# schematic.net
KiCad netlist of a schematic drawn in Altium Designer
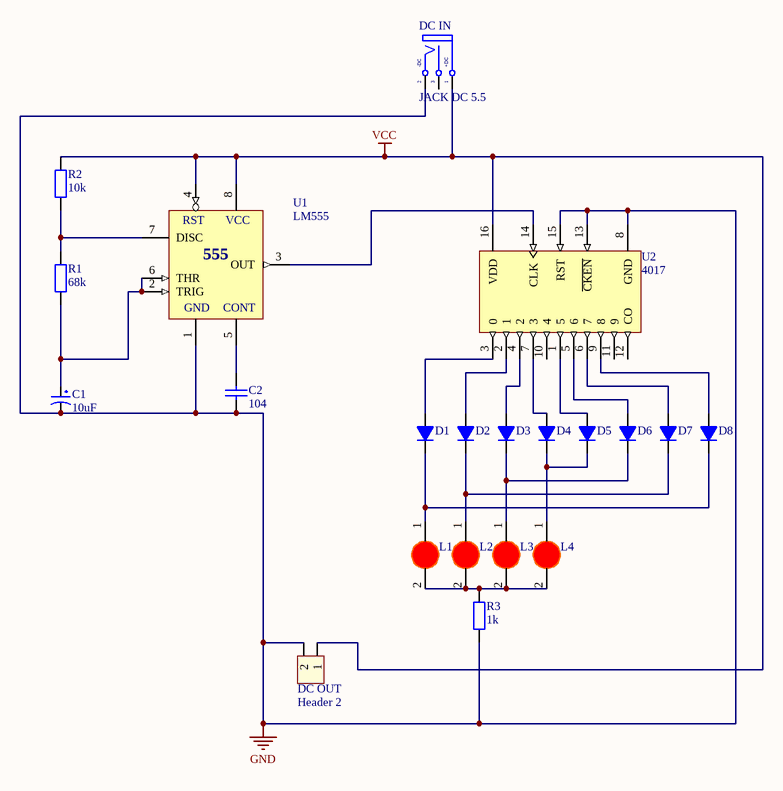
[diagram p0: schematic.SchDoc]

(export (version "E")
  (design (tool "Eeschema 10.0.6"))
  (components
    (comp (ref "C1")
      (value "10uF")
      (footprint "tu hoa 4mm")
      (description "Cắm")
      (libsource (lib "Capacitor") (part "Tu Hoa 10uF 16V 4x7"))
    )
    (comp (ref "C2")
      (value "104")
      (footprint "tu gom")
      (description "Cắm")
      (libsource (lib "Capacitor") (part "Tu gom 104 50V"))
    )
    (comp (ref "D1")
      (value "~")
      (footprint "DIODE 1A")
      (description "Cắm")
      (libsource (lib "Diode") (part "Diode 1N4007"))
    )
    (comp (ref "D2")
      (value "~")
      (footprint "DIODE 1A")
      (description "Cắm")
      (libsource (lib "Diode") (part "Diode 1N4007"))
    )
    (comp (ref "D3")
      (value "~")
      (footprint "DIODE 1A")
      (description "Cắm")
      (libsource (lib "Diode") (part "Diode 1N4007"))
    )
    (comp (ref "D4")
      (value "~")
      (footprint "DIODE 1A")
      (description "Cắm")
      (libsource (lib "Diode") (part "Diode 1N4007"))
    )
    (comp (ref "D5")
      (value "~")
      (footprint "DIODE 1A")
      (description "Cắm")
      (libsource (lib "Diode") (part "Diode 1N4007"))
    )
    (comp (ref "D6")
      (value "~")
      (footprint "DIODE 1A")
      (description "Cắm")
      (libsource (lib "Diode") (part "Diode 1N4007"))
    )
    (comp (ref "D7")
      (value "~")
      (footprint "DIODE 1A")
      (description "Cắm")
      (libsource (lib "Diode") (part "Diode 1N4007"))
    )
    (comp (ref "D8")
      (value "~")
      (footprint "DIODE 1A")
      (description "Cắm")
      (libsource (lib "Diode") (part "Diode 1N4007"))
    )
    (comp (ref "DC IN")
      (value "JACK DC 5.5")
      (footprint "JACK DC 5.5")
      (libsource (lib "Component") (part "JACK DC 5.5"))
    )
    (comp (ref "DC OUT")
      (value "Header 2")
      (footprint "HED2")
      (description "Header 2 (Green)")
      (libsource (lib "My Library") (part "Hed2"))
    )
    (comp (ref "L1")
      (value "~")
      (footprint "LED-3MM-RED")
      (description "Cắm")
      (libsource (lib "Led") (part "LED 3mm Do"))
    )
    (comp (ref "L2")
      (value "~")
      (footprint "LED-3MM-RED")
      (description "Cắm")
      (libsource (lib "Led") (part "LED 3mm Do"))
    )
    (comp (ref "L3")
      (value "~")
      (footprint "LED-3MM-RED")
      (description "Cắm")
      (libsource (lib "Led") (part "LED 3mm Do"))
    )
    (comp (ref "L4")
      (value "~")
      (footprint "LED-3MM-RED")
      (description "Cắm")
      (libsource (lib "Led") (part "LED 3mm Do"))
    )
    (comp (ref "R1")
      (value "68k")
      (footprint "tro vach 1/4w")
      (description "Cắm")
      (libsource (lib "Resistor") (part "Tro Vach 1/4W 5% 68k"))
    )
    (comp (ref "R2")
      (value "10k")
      (footprint "tro vach 1w")
      (description "Cắm")
      (libsource (lib "Resistor") (part "Tro Vach 1W 5% 10k"))
    )
    (comp (ref "R3")
      (value "1k")
      (footprint "tro vach 1w")
      (description "Cắm")
      (libsource (lib "Resistor") (part "Tro Vach 1W 5% 1k"))
    )
    (comp (ref "U1")
      (value "LM555")
      (footprint "DIP8/W0.3")
      (description "Timer")
      (libsource (lib "My Library") (part "LM555"))
    )
    (comp (ref "U2")
      (value "4017")
      (footprint "DIP16/W0.3")
      (description "Decade Counter/Divider with 10 Decoded Outputs")
      (fields (field (name "DESIGNED BY") "VanDungEvn"))
      (libsource (lib "My Library") (part "4017"))
    )
  )
  (nets
    (net (code "1") (name "GND") (class "Default")
      (node (ref "C1") (pin "2") (pinfunction "2_2") (pintype "passive"))
      (node (ref "C2") (pin "2") (pinfunction "2_2") (pintype "passive"))
      (node (ref "DC IN") (pin "2") (pinfunction "TN_2") (pintype "passive"))
      (node (ref "DC OUT") (pin "2") (pinfunction "2_2") (pintype "passive"))
      (node (ref "R3") (pin "1") (pinfunction "1_1") (pintype "passive"))
      (node (ref "U1") (pin "1") (pinfunction "GND_1") (pintype "power_in"))
      (node (ref "U2") (pin "13") (pinfunction "~{CKEN}_13") (pintype "input"))
      (node (ref "U2") (pin "15") (pinfunction "RST_15") (pintype "input"))
      (node (ref "U2") (pin "8") (pinfunction "GND_8") (pintype "power_in"))
    )
    (net (code "2") (name "Net-(D1-A)") (class "Default")
      (node (ref "D1") (pin "1") (pinfunction "A_1") (pintype "passive"))
      (node (ref "U2") (pin "3") (pinfunction "0_3") (pintype "output"))
    )
    (net (code "3") (name "Net-(D1-K)") (class "Default")
      (node (ref "D1") (pin "2") (pinfunction "K_2") (pintype "passive"))
      (node (ref "D8") (pin "2") (pinfunction "K_2") (pintype "passive"))
      (node (ref "L1") (pin "1") (pinfunction "A_1") (pintype "passive"))
    )
    (net (code "4") (name "Net-(D2-A)") (class "Default")
      (node (ref "D2") (pin "1") (pinfunction "A_1") (pintype "passive"))
      (node (ref "U2") (pin "2") (pinfunction "1_2") (pintype "output"))
    )
    (net (code "5") (name "Net-(D2-K)") (class "Default")
      (node (ref "D2") (pin "2") (pinfunction "K_2") (pintype "passive"))
      (node (ref "D7") (pin "2") (pinfunction "K_2") (pintype "passive"))
      (node (ref "L2") (pin "1") (pinfunction "A_1") (pintype "passive"))
    )
    (net (code "6") (name "Net-(D3-A)") (class "Default")
      (node (ref "D3") (pin "1") (pinfunction "A_1") (pintype "passive"))
      (node (ref "U2") (pin "4") (pinfunction "2_4") (pintype "output"))
    )
    (net (code "7") (name "Net-(D3-K)") (class "Default")
      (node (ref "D3") (pin "2") (pinfunction "K_2") (pintype "passive"))
      (node (ref "D6") (pin "2") (pinfunction "K_2") (pintype "passive"))
      (node (ref "L3") (pin "1") (pinfunction "A_1") (pintype "passive"))
    )
    (net (code "8") (name "Net-(D4-A)") (class "Default")
      (node (ref "D4") (pin "1") (pinfunction "A_1") (pintype "passive"))
      (node (ref "U2") (pin "7") (pinfunction "3_7") (pintype "output"))
    )
    (net (code "9") (name "Net-(D4-K)") (class "Default")
      (node (ref "D4") (pin "2") (pinfunction "K_2") (pintype "passive"))
      (node (ref "D5") (pin "2") (pinfunction "K_2") (pintype "passive"))
      (node (ref "L4") (pin "1") (pinfunction "A_1") (pintype "passive"))
    )
    (net (code "10") (name "Net-(D5-A)") (class "Default")
      (node (ref "D5") (pin "1") (pinfunction "A_1") (pintype "passive"))
      (node (ref "U2") (pin "1") (pinfunction "5_1") (pintype "output"))
    )
    (net (code "11") (name "Net-(D6-A)") (class "Default")
      (node (ref "D6") (pin "1") (pinfunction "A_1") (pintype "passive"))
      (node (ref "U2") (pin "5") (pinfunction "6_5") (pintype "output"))
    )
    (net (code "12") (name "Net-(D7-A)") (class "Default")
      (node (ref "D7") (pin "1") (pinfunction "A_1") (pintype "passive"))
      (node (ref "U2") (pin "6") (pinfunction "7_6") (pintype "output"))
    )
    (net (code "13") (name "Net-(D8-A)") (class "Default")
      (node (ref "D8") (pin "1") (pinfunction "A_1") (pintype "passive"))
      (node (ref "U2") (pin "9") (pinfunction "8_9") (pintype "output"))
    )
    (net (code "14") (name "Net-(L1-K)") (class "Default")
      (node (ref "L1") (pin "2") (pinfunction "K_2") (pintype "passive"))
      (node (ref "L2") (pin "2") (pinfunction "K_2") (pintype "passive"))
      (node (ref "L3") (pin "2") (pinfunction "K_2") (pintype "passive"))
      (node (ref "L4") (pin "2") (pinfunction "K_2") (pintype "passive"))
      (node (ref "R3") (pin "2") (pinfunction "2_2") (pintype "passive"))
    )
    (net (code "15") (name "Net-(U1-CONT)") (class "Default")
      (node (ref "C2") (pin "1") (pinfunction "1_1") (pintype "passive"))
      (node (ref "U1") (pin "5") (pinfunction "CONT_5") (pintype "passive"))
    )
    (net (code "16") (name "Net-(U1-DISC)") (class "Default")
      (node (ref "R1") (pin "2") (pinfunction "2_2") (pintype "passive"))
      (node (ref "R2") (pin "1") (pinfunction "1_1") (pintype "passive"))
      (node (ref "U1") (pin "7") (pinfunction "DISC_7") (pintype "open_collector"))
    )
    (net (code "17") (name "Net-(U1-OUT)") (class "Default")
      (node (ref "U1") (pin "3") (pinfunction "OUT_3") (pintype "output"))
      (node (ref "U2") (pin "14") (pinfunction "CLK_14") (pintype "input"))
    )
    (net (code "18") (name "Net-(U1-THR)") (class "Default")
      (node (ref "C1") (pin "1") (pinfunction "1_1") (pintype "passive"))
      (node (ref "R1") (pin "1") (pinfunction "1_1") (pintype "passive"))
      (node (ref "U1") (pin "2") (pinfunction "TRIG_2") (pintype "input"))
      (node (ref "U1") (pin "6") (pinfunction "THR_6") (pintype "input"))
    )
    (net (code "19") (name "VCC") (class "Default")
      (node (ref "DC IN") (pin "1") (pinfunction "T_1") (pintype "passive"))
      (node (ref "DC OUT") (pin "1") (pinfunction "1_1") (pintype "passive"))
      (node (ref "R2") (pin "2") (pinfunction "2_2") (pintype "passive"))
      (node (ref "U1") (pin "4") (pinfunction "RST_4") (pintype "input"))
      (node (ref "U1") (pin "8") (pinfunction "VCC_8") (pintype "power_in"))
      (node (ref "U2") (pin "16") (pinfunction "VDD_16") (pintype "power_in"))
    )
    (net (code "20") (name "unconnected-(DC IN-S-Pad3)") (class "Default")
      (node (ref "DC IN") (pin "3") (pinfunction "S_3") (pintype "power_in"))
    )
    (net (code "21") (name "unconnected-(U2-4-Pad10)") (class "Default")
      (node (ref "U2") (pin "10") (pinfunction "4_10") (pintype "output"))
    )
    (net (code "22") (name "unconnected-(U2-9-Pad11)") (class "Default")
      (node (ref "U2") (pin "11") (pinfunction "9_11") (pintype "output"))
    )
    (net (code "23") (name "unconnected-(U2-CO-Pad12)") (class "Default")
      (node (ref "U2") (pin "12") (pinfunction "CO_12") (pintype "output"))
    )
  )
)
